# Sheet2.net
KiCad netlist of a schematic drawn in Altium Designer
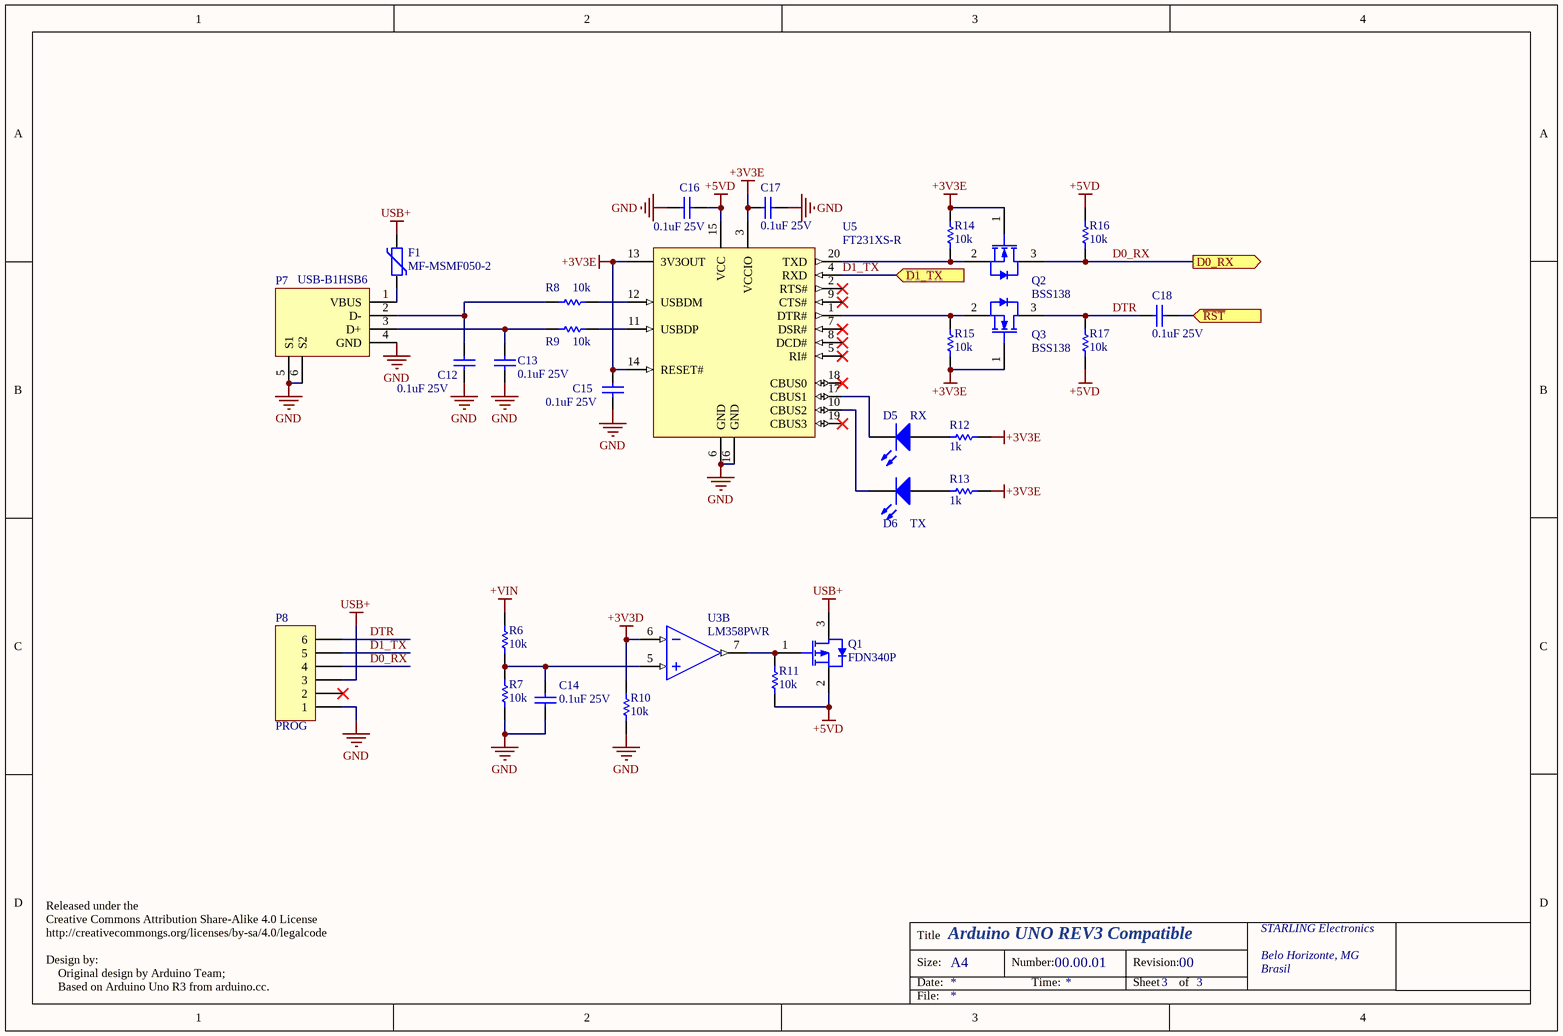
[diagram p0: Sheet2.SchDoc]

(export (version "E")
  (design (tool "Eeschema 10.0.6"))
  (components
    (comp (ref "C12")
      (value "0.1uF 25V")
      (footprint "C1608[0603]")
      (description "Capacitor")
      (fields (field (name "MANUFACTURER PART NUMBER") "GCM188R71E104KA57D") (field (name "TOLERANCE") "10%"))
      (libsource (lib "Basic Library") (part "C"))
    )
    (comp (ref "C13")
      (value "0.1uF 25V")
      (footprint "C1608[0603]")
      (description "Capacitor")
      (fields (field (name "MANUFACTURER PART NUMBER") "GCM188R71E104KA57D") (field (name "TOLERANCE") "10%"))
      (libsource (lib "Basic Library") (part "C"))
    )
    (comp (ref "C14")
      (value "0.1uF 25V")
      (footprint "C1608[0603]")
      (description "Capacitor")
      (fields (field (name "MANUFACTURER PART NUMBER") "GCM188R71E104KA57D") (field (name "TOLERANCE") "10%"))
      (libsource (lib "Basic Library") (part "C"))
    )
    (comp (ref "C15")
      (value "0.1uF 25V")
      (footprint "C1608[0603]")
      (description "Capacitor")
      (fields (field (name "MANUFACTURER PART NUMBER") "GCM188R71E104KA57D") (field (name "TOLERANCE") "10%"))
      (libsource (lib "Basic Library") (part "C"))
    )
    (comp (ref "C16")
      (value "0.1uF 25V")
      (footprint "C1608[0603]")
      (description "Capacitor")
      (fields (field (name "MANUFACTURER PART NUMBER") "GCM188R71E104KA57D") (field (name "TOLERANCE") "10%"))
      (libsource (lib "Basic Library") (part "C"))
    )
    (comp (ref "C17")
      (value "0.1uF 25V")
      (footprint "C1608[0603]")
      (description "Capacitor")
      (fields (field (name "MANUFACTURER PART NUMBER") "GCM188R71E104KA57D") (field (name "TOLERANCE") "10%"))
      (libsource (lib "Basic Library") (part "C"))
    )
    (comp (ref "C18")
      (value "0.1uF 25V")
      (footprint "C1608[0603]")
      (description "Capacitor")
      (fields (field (name "MANUFACTURER PART NUMBER") "GCM188R71E104KA57D") (field (name "TOLERANCE") "10%"))
      (libsource (lib "Basic Library") (part "C"))
    )
    (comp (ref "D5")
      (value "RX")
      (footprint "LED-0603-R")
      (description "LED")
      (fields (field (name "MANUFACTURER PART NUMBER") "LTST-C190KSKT"))
      (libsource (lib "Basic Library") (part "LED"))
    )
    (comp (ref "D6")
      (value "TX")
      (footprint "LED-0603-R")
      (description "LED")
      (fields (field (name "MANUFACTURER PART NUMBER") "LTST-C190KSKT"))
      (libsource (lib "Basic Library") (part "LED"))
    )
    (comp (ref "F1")
      (value "MF-MSMF050-2")
      (footprint "MF-MSMF050")
      (description "Resettable Fuse")
      (libsource (lib "Components Library") (part "MF-MSMF050-2"))
    )
    (comp (ref "P7")
      (value "USB-B1HSB6")
      (footprint "USB_Type_B")
      (fields (field (name "MANUFACTURER") "On-Shore Technology"))
      (libsource (lib "Connectors Library") (part "USB Type B"))
    )
    (comp (ref "P8")
      (value "PROG")
      (footprint "HDR1X6m")
      (description "Header, 6-Pin")
      (fields
        (field (name "MANUFACTURER") "Amphenol FCI")
        (field (name "MANUFACTURER PART NUMBER") "68000-406HLF")
        (field (name "PUBLISHER") "Altium Limited")
      )
      (libsource (lib "Connectors Library") (part "Header 6"))
    )
    (comp (ref "Q1")
      (value "FDN340P")
      (footprint "SOT23")
      (description "P-Channel MOSFET")
      (libsource (lib "Basic Library") (part "MOSFET-P"))
    )
    (comp (ref "Q2")
      (value "BSS138")
      (footprint "SOT23")
      (description "N-Channel MOSFET")
      (libsource (lib "Basic Library") (part "MOSFET-N"))
    )
    (comp (ref "Q3")
      (value "BSS138")
      (footprint "SOT23")
      (description "N-Channel MOSFET")
      (libsource (lib "Basic Library") (part "MOSFET-N"))
    )
    (comp (ref "R6")
      (value "10k")
      (footprint "R1608[0603]")
      (description "Resistor")
      (fields (field (name "MANUFACTURER PART NUMBER") "MCT06030C1002FP500") (field (name "TOLERANCE") "1%"))
      (libsource (lib "Basic Library") (part "R"))
    )
    (comp (ref "R7")
      (value "10k")
      (footprint "R1608[0603]")
      (description "Resistor")
      (fields (field (name "MANUFACTURER PART NUMBER") "MCT06030C1002FP500") (field (name "TOLERANCE") "1%"))
      (libsource (lib "Basic Library") (part "R"))
    )
    (comp (ref "R8")
      (value "10k")
      (footprint "R1608[0603]")
      (description "Resistor")
      (fields (field (name "MANUFACTURER PART NUMBER") "MCT06030C1002FP500") (field (name "TOLERANCE") "1%"))
      (libsource (lib "Basic Library") (part "R"))
    )
    (comp (ref "R9")
      (value "10k")
      (footprint "R1608[0603]")
      (description "Resistor")
      (fields (field (name "MANUFACTURER PART NUMBER") "MCT06030C1002FP500") (field (name "TOLERANCE") "1%"))
      (libsource (lib "Basic Library") (part "R"))
    )
    (comp (ref "R10")
      (value "10k")
      (footprint "R1608[0603]")
      (description "Resistor")
      (fields (field (name "MANUFACTURER PART NUMBER") "MCT06030C1002FP500") (field (name "TOLERANCE") "1%"))
      (libsource (lib "Basic Library") (part "R"))
    )
    (comp (ref "R11")
      (value "10k")
      (footprint "R1608[0603]")
      (description "Resistor")
      (fields (field (name "MANUFACTURER PART NUMBER") "MCT06030C1002FP500") (field (name "TOLERANCE") "1%"))
      (libsource (lib "Basic Library") (part "R"))
    )
    (comp (ref "R12")
      (value "1k")
      (footprint "R1608[0603]")
      (description "Resistor")
      (fields (field (name "MANUFACTURER PART NUMBER") "ESR03EZPJ102") (field (name "TOLERANCE") "5%"))
      (libsource (lib "Basic Library") (part "R"))
    )
    (comp (ref "R13")
      (value "1k")
      (footprint "R1608[0603]")
      (description "Resistor")
      (fields (field (name "MANUFACTURER PART NUMBER") "ESR03EZPJ102") (field (name "TOLERANCE") "5%"))
      (libsource (lib "Basic Library") (part "R"))
    )
    (comp (ref "R14")
      (value "10k")
      (footprint "R1608[0603]")
      (description "Resistor")
      (fields (field (name "MANUFACTURER PART NUMBER") "MCT06030C1002FP500") (field (name "TOLERANCE") "1%"))
      (libsource (lib "Basic Library") (part "R"))
    )
    (comp (ref "R15")
      (value "10k")
      (footprint "R1608[0603]")
      (description "Resistor")
      (fields (field (name "MANUFACTURER PART NUMBER") "MCT06030C1002FP500") (field (name "TOLERANCE") "1%"))
      (libsource (lib "Basic Library") (part "R"))
    )
    (comp (ref "R16")
      (value "10k")
      (footprint "R1608[0603]")
      (description "Resistor")
      (fields (field (name "MANUFACTURER PART NUMBER") "MCT06030C1002FP500") (field (name "TOLERANCE") "1%"))
      (libsource (lib "Basic Library") (part "R"))
    )
    (comp (ref "R17")
      (value "10k")
      (footprint "R1608[0603]")
      (description "Resistor")
      (fields (field (name "MANUFACTURER PART NUMBER") "MCT06030C1002FP500") (field (name "TOLERANCE") "1%"))
      (libsource (lib "Basic Library") (part "R"))
    )
    (comp (ref "U3")
      (value "LM358PWR")
      (footprint "TSSOP8-1")
      (fields (field (name "MANUFACTURER") "Texas Instruments"))
      (libsource (lib "Components Library") (part "LM358PWR"))
    )
    (comp (ref "U5")
      (value "FT231XS-R")
      (footprint "NSSOP-20_N")
      (fields (field (name "MANUFACTURER") "FTDI"))
      (libsource (lib "Components Library") (part "FT231XS-R"))
    )
  )
  (nets
    (net (code "1") (name "+3V3D") (class "Default")
      (node (ref "R10") (pin "1") (pinfunction "1_1") (pintype "passive"))
      (node (ref "U3") (pin "6") (pinfunction "IN2-_6") (pintype "input"))
    )
    (net (code "2") (name "+3V3E") (class "Default")
      (node (ref "C15") (pin "2") (pinfunction "2_2") (pintype "passive"))
      (node (ref "C17") (pin "2") (pinfunction "2_2") (pintype "passive"))
      (node (ref "Q2") (pin "1") (pinfunction "GATE_1") (pintype "passive"))
      (node (ref "Q3") (pin "1") (pinfunction "GATE_1") (pintype "passive"))
      (node (ref "R12") (pin "2") (pinfunction "2_2") (pintype "passive"))
      (node (ref "R13") (pin "2") (pinfunction "2_2") (pintype "passive"))
      (node (ref "R14") (pin "1") (pinfunction "1_1") (pintype "passive"))
      (node (ref "R15") (pin "2") (pinfunction "2_2") (pintype "passive"))
      (node (ref "U5") (pin "13") (pinfunction "3V3OUT_13") (pintype "power_in"))
      (node (ref "U5") (pin "14") (pinfunction "RESET#_14") (pintype "input"))
      (node (ref "U5") (pin "3") (pinfunction "VCCIO_3") (pintype "power_in"))
    )
    (net (code "3") (name "+5VD") (class "Default")
      (node (ref "C16") (pin "1") (pinfunction "1_1") (pintype "passive"))
      (node (ref "Q1") (pin "2") (pinfunction "SOURCE_2") (pintype "passive"))
      (node (ref "R11") (pin "2") (pinfunction "2_2") (pintype "passive"))
      (node (ref "R16") (pin "1") (pinfunction "1_1") (pintype "passive"))
      (node (ref "R17") (pin "2") (pinfunction "2_2") (pintype "passive"))
      (node (ref "U5") (pin "15") (pinfunction "VCC_15") (pintype "power_in"))
    )
    (net (code "4") (name "+VIN") (class "Default")
      (node (ref "R6") (pin "1") (pinfunction "1_1") (pintype "passive"))
    )
    (net (code "5") (name "/D0_RX") (class "Default")
      (node (ref "P8") (pin "4") (pinfunction "4_4") (pintype "passive"))
      (node (ref "Q2") (pin "3") (pinfunction "DRAIN_3") (pintype "passive"))
      (node (ref "R16") (pin "2") (pinfunction "2_2") (pintype "passive"))
    )
    (net (code "6") (name "/D1_TX") (class "Default")
      (node (ref "P8") (pin "5") (pinfunction "5_5") (pintype "passive"))
      (node (ref "U5") (pin "4") (pinfunction "RXD_4") (pintype "input"))
    )
    (net (code "7") (name "/DTR") (class "Default")
      (node (ref "C18") (pin "1") (pinfunction "1_1") (pintype "passive"))
      (node (ref "P8") (pin "6") (pinfunction "6_6") (pintype "passive"))
      (node (ref "Q3") (pin "3") (pinfunction "DRAIN_3") (pintype "passive"))
      (node (ref "R17") (pin "1") (pinfunction "1_1") (pintype "passive"))
    )
    (net (code "8") (name "/~{RST}") (class "Default")
      (node (ref "C18") (pin "2") (pinfunction "2_2") (pintype "passive"))
    )
    (net (code "9") (name "GND") (class "Default")
      (node (ref "C12") (pin "2") (pinfunction "2_2") (pintype "passive"))
      (node (ref "C13") (pin "2") (pinfunction "2_2") (pintype "passive"))
      (node (ref "C14") (pin "1") (pinfunction "1_1") (pintype "passive"))
      (node (ref "C15") (pin "1") (pinfunction "1_1") (pintype "passive"))
      (node (ref "C16") (pin "2") (pinfunction "2_2") (pintype "passive"))
      (node (ref "C17") (pin "1") (pinfunction "1_1") (pintype "passive"))
      (node (ref "P7") (pin "4") (pinfunction "GND_4") (pintype "passive"))
      (node (ref "P7") (pin "5") (pinfunction "S1_5") (pintype "passive"))
      (node (ref "P7") (pin "6") (pinfunction "S2_6") (pintype "passive"))
      (node (ref "P8") (pin "1") (pinfunction "1_1") (pintype "passive"))
      (node (ref "R10") (pin "2") (pinfunction "2_2") (pintype "passive"))
      (node (ref "R7") (pin "2") (pinfunction "2_2") (pintype "passive"))
      (node (ref "U5") (pin "16") (pinfunction "GND_16") (pintype "power_in"))
      (node (ref "U5") (pin "6") (pinfunction "GND_6") (pintype "power_in"))
    )
    (net (code "10") (name "Net-(D5-A)") (class "Default")
      (node (ref "D5") (pin "1") (pinfunction "A_1") (pintype "passive"))
      (node (ref "R12") (pin "1") (pinfunction "1_1") (pintype "passive"))
    )
    (net (code "11") (name "Net-(D5-K)") (class "Default")
      (node (ref "D5") (pin "2") (pinfunction "K_2") (pintype "passive"))
      (node (ref "U5") (pin "17") (pinfunction "CBUS1_17") (pintype "bidirectional"))
    )
    (net (code "12") (name "Net-(D6-A)") (class "Default")
      (node (ref "D6") (pin "1") (pinfunction "A_1") (pintype "passive"))
      (node (ref "R13") (pin "1") (pinfunction "1_1") (pintype "passive"))
    )
    (net (code "13") (name "Net-(D6-K)") (class "Default")
      (node (ref "D6") (pin "2") (pinfunction "K_2") (pintype "passive"))
      (node (ref "U5") (pin "10") (pinfunction "CBUS2_10") (pintype "bidirectional"))
    )
    (net (code "14") (name "Net-(P7-D+)") (class "Default")
      (node (ref "C13") (pin "1") (pinfunction "1_1") (pintype "passive"))
      (node (ref "P7") (pin "3") (pinfunction "D+_3") (pintype "passive"))
      (node (ref "R9") (pin "2") (pinfunction "2_2") (pintype "passive"))
    )
    (net (code "15") (name "Net-(P7-D-)") (class "Default")
      (node (ref "C12") (pin "1") (pinfunction "1_1") (pintype "passive"))
      (node (ref "P7") (pin "2") (pinfunction "D-_2") (pintype "passive"))
      (node (ref "R8") (pin "2") (pinfunction "2_2") (pintype "passive"))
    )
    (net (code "16") (name "Net-(P7-VBUS)") (class "Default")
      (node (ref "F1") (pin "1") (pinfunction "1_1") (pintype "passive"))
      (node (ref "P7") (pin "1") (pinfunction "VBUS_1") (pintype "passive"))
    )
    (net (code "17") (name "Net-(Q1-GATE)") (class "Default")
      (node (ref "Q1") (pin "1") (pinfunction "GATE_1") (pintype "passive"))
      (node (ref "R11") (pin "1") (pinfunction "1_1") (pintype "passive"))
      (node (ref "U3") (pin "7") (pinfunction "OUT2_7") (pintype "output"))
    )
    (net (code "18") (name "Net-(Q2-SOURCE)") (class "Default")
      (node (ref "Q2") (pin "2") (pinfunction "SOURCE_2") (pintype "passive"))
      (node (ref "R14") (pin "2") (pinfunction "2_2") (pintype "passive"))
      (node (ref "U5") (pin "20") (pinfunction "TXD_20") (pintype "output"))
    )
    (net (code "19") (name "Net-(Q3-SOURCE)") (class "Default")
      (node (ref "Q3") (pin "2") (pinfunction "SOURCE_2") (pintype "passive"))
      (node (ref "R15") (pin "1") (pinfunction "1_1") (pintype "passive"))
      (node (ref "U5") (pin "1") (pinfunction "DTR#_1") (pintype "output"))
    )
    (net (code "20") (name "Net-(U3B-IN2+)") (class "Default")
      (node (ref "C14") (pin "2") (pinfunction "2_2") (pintype "passive"))
      (node (ref "R6") (pin "2") (pinfunction "2_2") (pintype "passive"))
      (node (ref "R7") (pin "1") (pinfunction "1_1") (pintype "passive"))
      (node (ref "U3") (pin "5") (pinfunction "IN2+_5") (pintype "input"))
    )
    (net (code "21") (name "Net-(U5-USBDM)") (class "Default")
      (node (ref "R8") (pin "1") (pinfunction "1_1") (pintype "passive"))
      (node (ref "U5") (pin "12") (pinfunction "USBDM_12") (pintype "input"))
    )
    (net (code "22") (name "Net-(U5-USBDP)") (class "Default")
      (node (ref "R9") (pin "1") (pinfunction "1_1") (pintype "passive"))
      (node (ref "U5") (pin "11") (pinfunction "USBDP_11") (pintype "input"))
    )
    (net (code "23") (name "USB+") (class "Default")
      (node (ref "F1") (pin "2") (pinfunction "2_2") (pintype "passive"))
      (node (ref "P8") (pin "3") (pinfunction "3_3") (pintype "passive"))
      (node (ref "Q1") (pin "3") (pinfunction "DRAIN_3") (pintype "passive"))
    )
    (net (code "24") (name "unconnected-(P8-Pad2)") (class "Default")
      (node (ref "P8") (pin "2") (pinfunction "2_2") (pintype "passive+no_connect"))
    )
    (net (code "25") (name "unconnected-(U5-CBUS0-Pad18)") (class "Default")
      (node (ref "U5") (pin "18") (pinfunction "CBUS0_18") (pintype "bidirectional+no_connect"))
    )
    (net (code "26") (name "unconnected-(U5-CBUS3-Pad19)") (class "Default")
      (node (ref "U5") (pin "19") (pinfunction "CBUS3_19") (pintype "bidirectional+no_connect"))
    )
    (net (code "27") (name "unconnected-(U5-CTS#-Pad9)") (class "Default")
      (node (ref "U5") (pin "9") (pinfunction "CTS#_9") (pintype "input+no_connect"))
    )
    (net (code "28") (name "unconnected-(U5-DCD#-Pad8)") (class "Default")
      (node (ref "U5") (pin "8") (pinfunction "DCD#_8") (pintype "input+no_connect"))
    )
    (net (code "29") (name "unconnected-(U5-DSR#-Pad7)") (class "Default")
      (node (ref "U5") (pin "7") (pinfunction "DSR#_7") (pintype "input+no_connect"))
    )
    (net (code "30") (name "unconnected-(U5-RI#-Pad5)") (class "Default")
      (node (ref "U5") (pin "5") (pinfunction "RI#_5") (pintype "input+no_connect"))
    )
    (net (code "31") (name "unconnected-(U5-RTS#-Pad2)") (class "Default")
      (node (ref "U5") (pin "2") (pinfunction "RTS#_2") (pintype "output+no_connect"))
    )
  )
)
